# GlowWorm.net
KiCad netlist of a schematic drawn in EAGLE
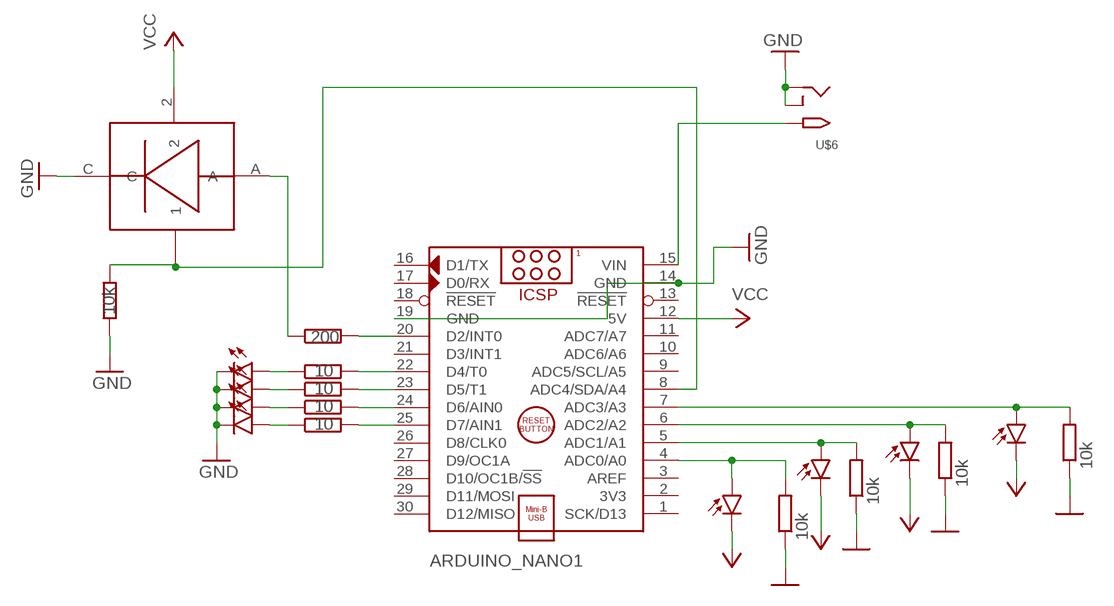
[diagram p0: schematic, sheet 1]

(export (version "E")
  (design (tool "Eeschema 10.0.6"))
  (components
    (comp (ref "ARDUINO_NANO1")
      (value "ARDUINO_NANO")
      (footprint "eagle-import:ARDUINO_NANO")
      (libsource (lib "eagle-import") (part "ARDUINO_NANO"))
    )
    (comp (ref "R1")
      (value "10")
      (footprint "eagle-import:0207_7")
      (libsource (lib "eagle-import") (part "R-EU_0207/7"))
    )
    (comp (ref "R2")
      (value "10k")
      (footprint "eagle-import:0207_7")
      (libsource (lib "eagle-import") (part "R-EU_0207/7"))
    )
    (comp (ref "R5")
      (value "10k")
      (footprint "eagle-import:0207_7")
      (libsource (lib "eagle-import") (part "R-EU_0207/7"))
    )
    (comp (ref "R6")
      (value "10k")
      (footprint "eagle-import:0207_7")
      (libsource (lib "eagle-import") (part "R-EU_0207/7"))
    )
    (comp (ref "R7")
      (value "10k")
      (footprint "eagle-import:0207_7")
      (libsource (lib "eagle-import") (part "R-EU_0207/7"))
    )
    (comp (ref "R11")
      (value "200")
      (footprint "eagle-import:0207_7")
      (libsource (lib "eagle-import") (part "R-EU_0207/7"))
    )
    (comp (ref "R12")
      (value "10")
      (footprint "eagle-import:0207_7")
      (libsource (lib "eagle-import") (part "R-EU_0207/7"))
    )
    (comp (ref "R13")
      (value "10")
      (footprint "eagle-import:0207_7")
      (libsource (lib "eagle-import") (part "R-EU_0207/7"))
    )
    (comp (ref "R14")
      (value "10")
      (footprint "eagle-import:0207_7")
      (libsource (lib "eagle-import") (part "R-EU_0207/7"))
    )
    (comp (ref "R15")
      (value "10k")
      (footprint "eagle-import:0207_7")
      (libsource (lib "eagle-import") (part "R-EU_0207/7"))
    )
    (comp (ref "U$1")
      (value "IR_RECEIVER")
      (footprint "eagle-import:LED_RECEIVER5MM_H6,0MM")
      (libsource (lib "eagle-import") (part "IR_RECEIVER"))
    )
    (comp (ref "U$2")
      (value "IR_RECEIVER")
      (footprint "eagle-import:LED_RECEIVER5MM_H6,0MM")
      (libsource (lib "eagle-import") (part "IR_RECEIVER"))
    )
    (comp (ref "U$3")
      (value "IR_RECEIVER")
      (footprint "eagle-import:LED_RECEIVER5MM_H6,0MM")
      (libsource (lib "eagle-import") (part "IR_RECEIVER"))
    )
    (comp (ref "U$4")
      (value "IR_RECEIVER")
      (footprint "eagle-import:LED_RECEIVER5MM_H6,0MM")
      (libsource (lib "eagle-import") (part "IR_RECEIVER"))
    )
    (comp (ref "U$5")
      (value "IR_TRANSMITTER")
      (footprint "eagle-import:LED5MM_H6,0MM")
      (libsource (lib "eagle-import") (part "IR_TRANSMITTER"))
    )
    (comp (ref "U$6")
      (value "2.1MMJACKTHM")
      (footprint "eagle-import:PJ-102A")
      (libsource (lib "eagle-import") (part "2.1MMJACKTHM"))
    )
    (comp (ref "U$9")
      (value "ARCADE_LED_BTN")
      (footprint "eagle-import:ARCADE_LED_BTN")
      (libsource (lib "eagle-import") (part "ARCADE_LED_BTN"))
    )
    (comp (ref "U$10")
      (value "IR_TRANSMITTER")
      (footprint "eagle-import:LED5MM_H6,0MM")
      (libsource (lib "eagle-import") (part "IR_TRANSMITTER"))
    )
    (comp (ref "U$11")
      (value "IR_TRANSMITTER")
      (footprint "eagle-import:LED5MM_H6,0MM")
      (libsource (lib "eagle-import") (part "IR_TRANSMITTER"))
    )
    (comp (ref "U$12")
      (value "IR_TRANSMITTER")
      (footprint "eagle-import:LED5MM_H6,0MM")
      (libsource (lib "eagle-import") (part "IR_TRANSMITTER"))
    )
  )
  (nets
    (net (code "1") (name "GND") (class "Default")
      (node (ref "ARDUINO_NANO1") (pin "14") (pinfunction "GND_14") (pintype "power_in"))
      (node (ref "ARDUINO_NANO1") (pin "19") (pinfunction "GND_19") (pintype "power_in"))
      (node (ref "R15") (pin "1") (pinfunction "1_1") (pintype "passive"))
      (node (ref "R2") (pin "1") (pinfunction "1_1") (pintype "passive"))
      (node (ref "R5") (pin "1") (pinfunction "1_1") (pintype "passive"))
      (node (ref "R6") (pin "1") (pinfunction "1_1") (pintype "passive"))
      (node (ref "R7") (pin "1") (pinfunction "1_1") (pintype "passive"))
      (node (ref "U$10") (pin "K") (pinfunction "C_K") (pintype "passive"))
      (node (ref "U$11") (pin "K") (pinfunction "C_K") (pintype "passive"))
      (node (ref "U$12") (pin "K") (pinfunction "C_K") (pintype "passive"))
      (node (ref "U$5") (pin "K") (pinfunction "C_K") (pintype "passive"))
      (node (ref "U$6") (pin "RING") (pinfunction "RING_RING") (pintype "bidirectional"))
      (node (ref "U$6") (pin "RING_SW") (pinfunction "RING_SW_RING_SW") (pintype "bidirectional"))
      (node (ref "U$9") (pin "C") (pinfunction "C_C") (pintype "bidirectional"))
    )
    (net (code "2") (name "Net-(ARDUINO_NANO1-ADC0{slash}A0)") (class "Default")
      (node (ref "ARDUINO_NANO1") (pin "4") (pinfunction "ADC0/A0_4") (pintype "bidirectional"))
      (node (ref "R2") (pin "2") (pinfunction "2_2") (pintype "passive"))
      (node (ref "U$1") (pin "A") (pinfunction "ANODE_A") (pintype "passive"))
    )
    (net (code "3") (name "Net-(ARDUINO_NANO1-ADC1{slash}A1)") (class "Default")
      (node (ref "ARDUINO_NANO1") (pin "5") (pinfunction "ADC1/A1_5") (pintype "bidirectional"))
      (node (ref "R6") (pin "2") (pinfunction "2_2") (pintype "passive"))
      (node (ref "U$3") (pin "A") (pinfunction "ANODE_A") (pintype "passive"))
    )
    (net (code "4") (name "Net-(ARDUINO_NANO1-ADC2{slash}A2)") (class "Default")
      (node (ref "ARDUINO_NANO1") (pin "6") (pinfunction "ADC2/A2_6") (pintype "bidirectional"))
      (node (ref "R5") (pin "2") (pinfunction "2_2") (pintype "passive"))
      (node (ref "U$2") (pin "A") (pinfunction "ANODE_A") (pintype "passive"))
    )
    (net (code "5") (name "Net-(ARDUINO_NANO1-ADC3{slash}A3)") (class "Default")
      (node (ref "ARDUINO_NANO1") (pin "7") (pinfunction "ADC3/A3_7") (pintype "bidirectional"))
      (node (ref "R7") (pin "2") (pinfunction "2_2") (pintype "passive"))
      (node (ref "U$4") (pin "A") (pinfunction "ANODE_A") (pintype "passive"))
    )
    (net (code "6") (name "Net-(ARDUINO_NANO1-ADC4{slash}SDA{slash}A4)") (class "Default")
      (node (ref "ARDUINO_NANO1") (pin "8") (pinfunction "ADC4/SDA/A4_8") (pintype "bidirectional"))
      (node (ref "R15") (pin "2") (pinfunction "2_2") (pintype "passive"))
      (node (ref "U$9") (pin "1") (pinfunction "1_1") (pintype "bidirectional"))
    )
    (net (code "7") (name "Net-(ARDUINO_NANO1-D2{slash}INT0)") (class "Default")
      (node (ref "ARDUINO_NANO1") (pin "20") (pinfunction "D2/INT0_20") (pintype "bidirectional"))
      (node (ref "R11") (pin "2") (pinfunction "2_2") (pintype "passive"))
    )
    (net (code "8") (name "Net-(ARDUINO_NANO1-D4{slash}T0)") (class "Default")
      (node (ref "ARDUINO_NANO1") (pin "22") (pinfunction "D4/T0_22") (pintype "bidirectional"))
      (node (ref "R1") (pin "2") (pinfunction "2_2") (pintype "passive"))
    )
    (net (code "9") (name "Net-(ARDUINO_NANO1-D5{slash}T1)") (class "Default")
      (node (ref "ARDUINO_NANO1") (pin "23") (pinfunction "D5/T1_23") (pintype "bidirectional"))
      (node (ref "R12") (pin "2") (pinfunction "2_2") (pintype "passive"))
    )
    (net (code "10") (name "Net-(ARDUINO_NANO1-D6{slash}AIN0)") (class "Default")
      (node (ref "ARDUINO_NANO1") (pin "24") (pinfunction "D6/AIN0_24") (pintype "bidirectional"))
      (node (ref "R13") (pin "2") (pinfunction "2_2") (pintype "passive"))
    )
    (net (code "11") (name "Net-(ARDUINO_NANO1-D7{slash}AIN1)") (class "Default")
      (node (ref "ARDUINO_NANO1") (pin "25") (pinfunction "D7/AIN1_25") (pintype "bidirectional"))
      (node (ref "R14") (pin "2") (pinfunction "2_2") (pintype "passive"))
    )
    (net (code "12") (name "Net-(ARDUINO_NANO1-VIN)") (class "Default")
      (node (ref "ARDUINO_NANO1") (pin "15") (pinfunction "VIN_15") (pintype "power_in"))
      (node (ref "U$6") (pin "TIP") (pinfunction "TIP_TIP") (pintype "bidirectional"))
    )
    (net (code "13") (name "Net-(R1-Pad1)") (class "Default")
      (node (ref "R1") (pin "1") (pinfunction "1_1") (pintype "passive"))
      (node (ref "U$5") (pin "A") (pinfunction "A_A") (pintype "passive"))
    )
    (net (code "14") (name "Net-(R11-Pad1)") (class "Default")
      (node (ref "R11") (pin "1") (pinfunction "1_1") (pintype "passive"))
      (node (ref "U$9") (pin "A") (pinfunction "A_A") (pintype "bidirectional"))
    )
    (net (code "15") (name "Net-(R12-Pad1)") (class "Default")
      (node (ref "R12") (pin "1") (pinfunction "1_1") (pintype "passive"))
      (node (ref "U$10") (pin "A") (pinfunction "A_A") (pintype "passive"))
    )
    (net (code "16") (name "Net-(R13-Pad1)") (class "Default")
      (node (ref "R13") (pin "1") (pinfunction "1_1") (pintype "passive"))
      (node (ref "U$11") (pin "A") (pinfunction "A_A") (pintype "passive"))
    )
    (net (code "17") (name "Net-(R14-Pad1)") (class "Default")
      (node (ref "R14") (pin "1") (pinfunction "1_1") (pintype "passive"))
      (node (ref "U$12") (pin "A") (pinfunction "A_A") (pintype "passive"))
    )
    (net (code "18") (name "VCC") (class "Default")
      (node (ref "ARDUINO_NANO1") (pin "12") (pinfunction "5V_12") (pintype "power_in"))
      (node (ref "U$1") (pin "K") (pinfunction "CATHODE_K") (pintype "passive"))
      (node (ref "U$2") (pin "K") (pinfunction "CATHODE_K") (pintype "passive"))
      (node (ref "U$3") (pin "K") (pinfunction "CATHODE_K") (pintype "passive"))
      (node (ref "U$4") (pin "K") (pinfunction "CATHODE_K") (pintype "passive"))
      (node (ref "U$9") (pin "2") (pinfunction "2_2") (pintype "bidirectional"))
    )
    (net (code "19") (name "unconnected-(ARDUINO_NANO1-3V3-Pad2)") (class "Default")
      (node (ref "ARDUINO_NANO1") (pin "2") (pinfunction "3V3_2") (pintype "output"))
    )
    (net (code "20") (name "unconnected-(ARDUINO_NANO1-ADC5{slash}SCL{slash}A5-Pad9)") (class "Default")
      (node (ref "ARDUINO_NANO1") (pin "9") (pinfunction "ADC5/SCL/A5_9") (pintype "bidirectional"))
    )
    (net (code "21") (name "unconnected-(ARDUINO_NANO1-ADC6{slash}A6-Pad10)") (class "Default")
      (node (ref "ARDUINO_NANO1") (pin "10") (pinfunction "ADC6/A6_10") (pintype "bidirectional"))
    )
    (net (code "22") (name "unconnected-(ARDUINO_NANO1-ADC7{slash}A7-Pad11)") (class "Default")
      (node (ref "ARDUINO_NANO1") (pin "11") (pinfunction "ADC7/A7_11") (pintype "bidirectional"))
    )
    (net (code "23") (name "unconnected-(ARDUINO_NANO1-AREF-Pad3)") (class "Default")
      (node (ref "ARDUINO_NANO1") (pin "3") (pinfunction "AREF_3") (pintype "input"))
    )
    (net (code "24") (name "unconnected-(ARDUINO_NANO1-D0{slash}RX-Pad17)") (class "Default")
      (node (ref "ARDUINO_NANO1") (pin "17") (pinfunction "D0/RX_17") (pintype "bidirectional"))
    )
    (net (code "25") (name "unconnected-(ARDUINO_NANO1-D1{slash}TX-Pad16)") (class "Default")
      (node (ref "ARDUINO_NANO1") (pin "16") (pinfunction "D1/TX_16") (pintype "bidirectional"))
    )
    (net (code "26") (name "unconnected-(ARDUINO_NANO1-D3{slash}INT1-Pad21)") (class "Default")
      (node (ref "ARDUINO_NANO1") (pin "21") (pinfunction "D3/INT1_21") (pintype "bidirectional"))
    )
    (net (code "27") (name "unconnected-(ARDUINO_NANO1-D8{slash}CLK0-Pad26)") (class "Default")
      (node (ref "ARDUINO_NANO1") (pin "26") (pinfunction "D8/CLK0_26") (pintype "bidirectional"))
    )
    (net (code "28") (name "unconnected-(ARDUINO_NANO1-D9{slash}OC1A-Pad27)") (class "Default")
      (node (ref "ARDUINO_NANO1") (pin "27") (pinfunction "D9/OC1A_27") (pintype "bidirectional"))
    )
    (net (code "29") (name "unconnected-(ARDUINO_NANO1-D10{slash}OC1B{slash}~{SS}-Pad28)") (class "Default")
      (node (ref "ARDUINO_NANO1") (pin "28") (pinfunction "D10/OC1B/~{SS}_28") (pintype "bidirectional"))
    )
    (net (code "30") (name "unconnected-(ARDUINO_NANO1-D11{slash}MOSI-Pad29)") (class "Default")
      (node (ref "ARDUINO_NANO1") (pin "29") (pinfunction "D11/MOSI_29") (pintype "bidirectional"))
    )
    (net (code "31") (name "unconnected-(ARDUINO_NANO1-D12{slash}MISO-Pad30)") (class "Default")
      (node (ref "ARDUINO_NANO1") (pin "30") (pinfunction "D12/MISO_30") (pintype "bidirectional"))
    )
    (net (code "32") (name "unconnected-(ARDUINO_NANO1-SCK{slash}D13-Pad1)") (class "Default")
      (node (ref "ARDUINO_NANO1") (pin "1") (pinfunction "SCK/D13_1") (pintype "bidirectional"))
    )
    (net (code "33") (name "unconnected-(ARDUINO_NANO1-~{RESET}-Pad13)") (class "Default")
      (node (ref "ARDUINO_NANO1") (pin "13") (pinfunction "~{RESET}_13") (pintype "input"))
    )
    (net (code "34") (name "unconnected-(ARDUINO_NANO1-~{RESET}-Pad18)") (class "Default")
      (node (ref "ARDUINO_NANO1") (pin "18") (pinfunction "~{RESET}_18") (pintype "input"))
    )
  )
)
